# RF.net
KiCad netlist of a schematic drawn in Altium Designer
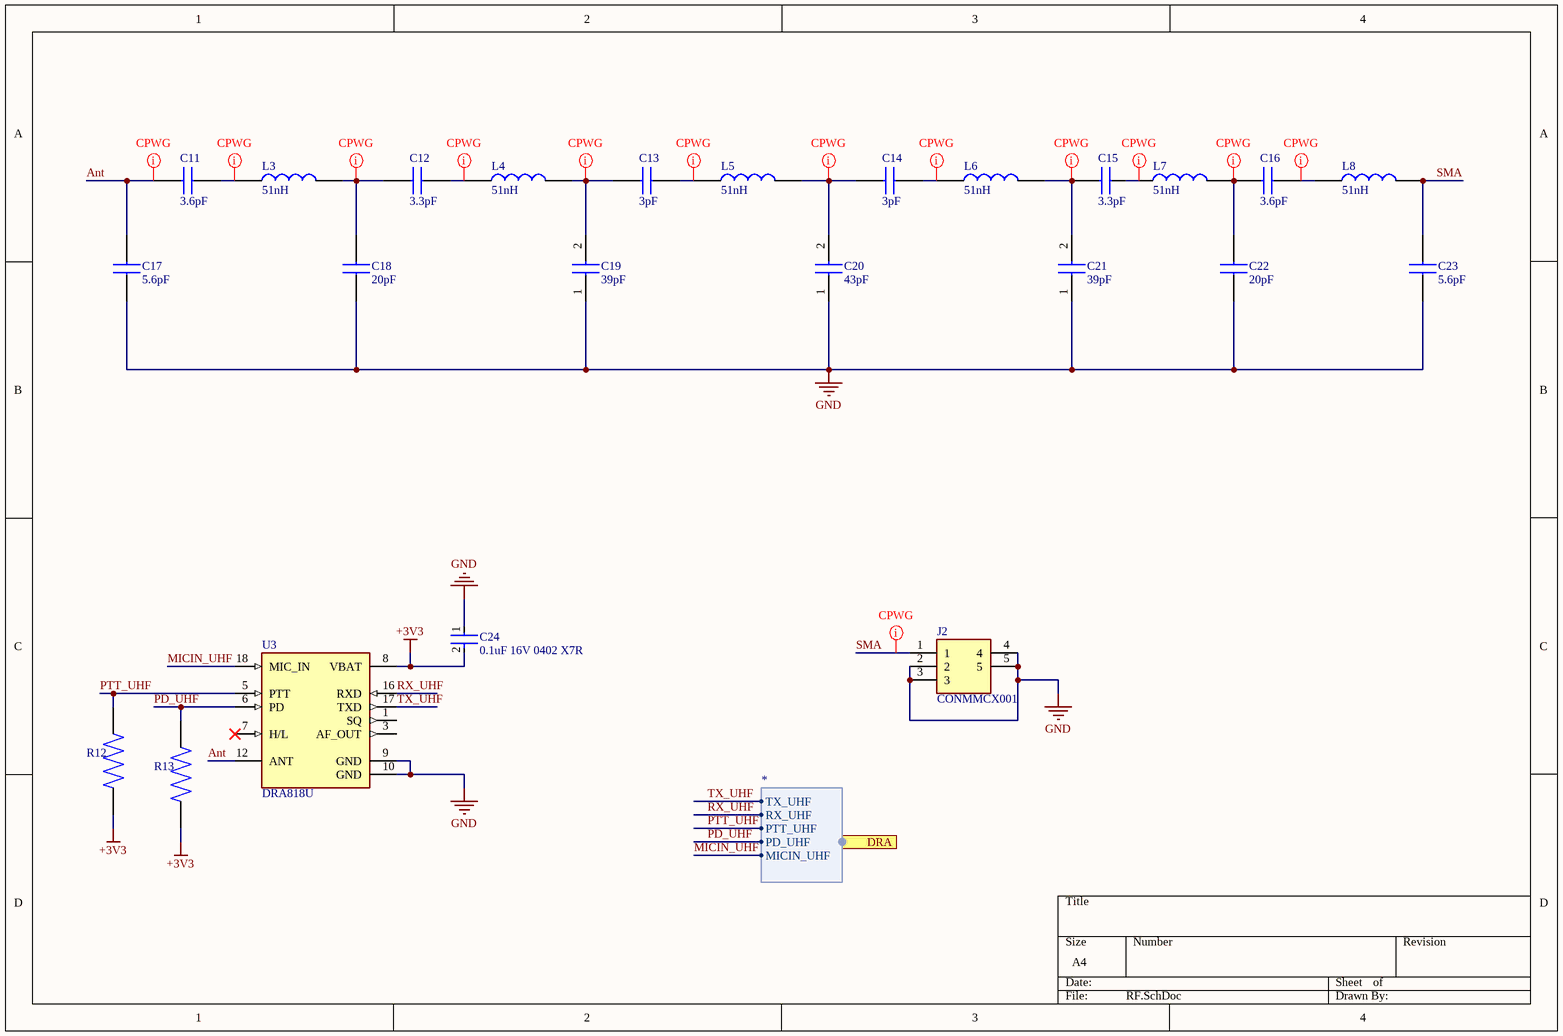
[diagram p0: RF.SchDoc]

(export (version "E")
  (design (tool "Eeschema 10.0.6"))
  (components
    (comp (ref "C11")
      (value "3.6pF")
      (footprint "CAP0603S")
      (fields (field (name "MANUFACTURER_PART_NUMBER") "CBR06C369BAGAC"))
      (libsource (lib "CBR06C369BAGAC") (part "CBR06C369BAGAC"))
    )
    (comp (ref "C12")
      (value "3.3pF")
      (footprint "CAP0603S")
      (description "Vishay 0603 VJ 3.3pF Ceramic Multilayer Capacitor, 250 V, +125C, COG Dielectric, +/-0.1pF SMD")
      (fields (field (name "MANUFACTURER_PART_NUMBER") "VJ0603D3R3BXPAJ"))
      (libsource (lib "VJ0603D3R3BXPAJ") (part "VJ0603D3R3BXPAJ"))
    )
    (comp (ref "C13")
      (value "3pF")
      (footprint "CAP0402S")
      (fields (field (name "MANUFACTURER_PART_NUMBER") "VJ0603D3R3BXPAJ"))
      (libsource (lib "VJ0603D3R3BXPAJ") (part "VJ0603D3R3BXPAJ"))
    )
    (comp (ref "C14")
      (value "3pF")
      (footprint "CAP0402S")
      (fields (field (name "MANUFACTURER_PART_NUMBER") "VJ0603D3R3BXPAJ"))
      (libsource (lib "VJ0603D3R3BXPAJ") (part "VJ0603D3R3BXPAJ"))
    )
    (comp (ref "C15")
      (value "3.3pF")
      (footprint "CAP0603S")
      (description "Vishay 0603 VJ 3.3pF Ceramic Multilayer Capacitor, 250 V, +125C, COG Dielectric, +/-0.1pF SMD")
      (fields (field (name "MANUFACTURER_PART_NUMBER") "VJ0603D3R3BXPAJ"))
      (libsource (lib "VJ0603D3R3BXPAJ") (part "VJ0603D3R3BXPAJ"))
    )
    (comp (ref "C16")
      (value "3.6pF")
      (footprint "CAP0603S")
      (fields (field (name "MANUFACTURER_PART_NUMBER") "CBR06C369BAGAC"))
      (libsource (lib "CBR06C369BAGAC") (part "CBR06C369BAGAC"))
    )
    (comp (ref "C17")
      (value "5.6pF")
      (footprint "CAP0603S")
      (description "AVX 0603 U 5.6pF Ceramic Multilayer Capacitor, 200 V dc, +125C, C0G Dielectric, +/-0.25pF SMD")
      (fields
        (field (name "MOUSER PART NUMBER") "581-06032U5R6CAT2A")
        (field (name "MANUFACTURER_PART_NUMBER") "06032U5R6CAT2A")
      )
      (libsource (lib "06032U5R6CAT2A") (part "06032U5R6CAT2A"))
    )
    (comp (ref "C18")
      (value "20pF")
      (footprint "CAP0603S")
      (fields (field (name "MANUFACTURER_PART_NUMBER") "CBR02C200F5GAC"))
      (libsource (lib "CBR02C200F5GAC") (part "CBR02C200F5GAC"))
    )
    (comp (ref "C19")
      (value "39pF")
      (footprint "CAP0603S")
      (description "Capacitor-C0603H390J5GACTU")
      (fields (field (name "MANUFACTURER_PART_NUMBER") "C0603H390J5GACTU"))
      (libsource (lib "*") (part "C0603H390J5GACTU"))
    )
    (comp (ref "C20")
      (value "43pF")
      (footprint "CAP0603S")
      (description "Capacitor")
      (fields
        (field (name "MANUFACTURER_PART_NUMBER") "CBR06C430J5GACAUTO")
        (field (name "MOUSER PART NUMBER") "80-CBR06C430J5GAUTO")
      )
      (libsource (lib "*") (part "CBR06C430J5GACAUTO"))
    )
    (comp (ref "C21")
      (value "39pF")
      (footprint "CAP0603S")
      (description "Capacitor")
      (fields (field (name "MANUFACTURER_PART_NUMBER") "C0603H390J5GACTU"))
      (libsource (lib "*") (part "C0603H390J5GACTU"))
    )
    (comp (ref "C22")
      (value "20pF")
      (footprint "CAP0603S")
      (fields (field (name "MANUFACTURER_PART_NUMBER") "CBR02C200F5GAC"))
      (libsource (lib "CBR02C200F5GAC") (part "CBR02C200F5GAC"))
    )
    (comp (ref "C23")
      (value "5.6pF")
      (footprint "CAP0603S")
      (description "AVX 0603 U 5.6pF Ceramic Multilayer Capacitor, 200 V dc, +125C, C0G Dielectric, +/-0.25pF SMD")
      (fields
        (field (name "MOUSER PART NUMBER") "581-06032U5R6CAT2A")
        (field (name "MANUFACTURER_PART_NUMBER") "06032U5R6CAT2A")
      )
      (libsource (lib "06032U5R6CAT2A") (part "06032U5R6CAT2A"))
    )
    (comp (ref "C24")
      (value "0.1uF 16V 0402 X7R")
      (footprint "CAP0402S")
      (description "CAP CER 0.1UF 16V X7R 0402")
      (fields (field (name "MANUFACTURER PART NUMBER") "GRM155R71C104KA88D") (field (name "TOLERANCE") "10%"))
      (libsource (lib "Miscellaneous Devices") (part "236180d848d6139a670b325ea6854c9"))
    )
    (comp (ref "J2")
      (value "CONMMCX001")
      (footprint "SAMTEC_MMCX-J-P-H-ST-SM1")
      (description "Body Features: Cable Connector Orientation Straight")
      (libsource (lib "CONMMCX001") (part "CONMMCX001"))
    )
    (comp (ref "L3")
      (value "51nH")
      (footprint "IND0603S")
      (description "Murata LQQ18A Series Wire-wound SMD Inductor with a Ferrite Core, 0.051 uH +/-2% 370mA Idc Q:38")
      (fields
        (field (name "MOUSER PART NUMBER") "81-LQW18AN51NG00D")
        (field (name "MANUFACTURER_PART_NUMBER") "LQW18AN51NG00D")
      )
      (libsource (lib "LQW18AN51NG00D") (part "LQW18AN51NG00D"))
    )
    (comp (ref "L4")
      (value "51nH")
      (footprint "IND0603S")
      (description "Murata LQQ18A Series Wire-wound SMD Inductor with a Ferrite Core, 0.051 uH +/-2% 370mA Idc Q:38")
      (fields
        (field (name "MOUSER PART NUMBER") "81-LQW18AN51NG00D")
        (field (name "MANUFACTURER_PART_NUMBER") "LQW18AN51NG00D")
      )
      (libsource (lib "LQW18AN51NG00D") (part "LQW18AN51NG00D"))
    )
    (comp (ref "L5")
      (value "51nH")
      (footprint "IND0603S")
      (description "Murata LQQ18A Series Wire-wound SMD Inductor with a Ferrite Core, 0.051 uH +/-2% 370mA Idc Q:38")
      (fields
        (field (name "MOUSER PART NUMBER") "81-LQW18AN51NG00D")
        (field (name "MANUFACTURER_PART_NUMBER") "LQW18AN51NG00D")
      )
      (libsource (lib "LQW18AN51NG00D") (part "LQW18AN51NG00D"))
    )
    (comp (ref "L6")
      (value "51nH")
      (footprint "IND0603S")
      (description "Murata LQQ18A Series Wire-wound SMD Inductor with a Ferrite Core, 0.051 uH +/-2% 370mA Idc Q:38")
      (fields
        (field (name "MOUSER PART NUMBER") "81-LQW18AN51NG00D")
        (field (name "MANUFACTURER_PART_NUMBER") "LQW18AN51NG00D")
      )
      (libsource (lib "LQW18AN51NG00D") (part "LQW18AN51NG00D"))
    )
    (comp (ref "L7")
      (value "51nH")
      (footprint "IND0603S")
      (description "Murata LQQ18A Series Wire-wound SMD Inductor with a Ferrite Core, 0.051 uH +/-2% 370mA Idc Q:38")
      (fields
        (field (name "MOUSER PART NUMBER") "81-LQW18AN51NG00D")
        (field (name "MANUFACTURER_PART_NUMBER") "LQW18AN51NG00D")
      )
      (libsource (lib "LQW18AN51NG00D") (part "LQW18AN51NG00D"))
    )
    (comp (ref "L8")
      (value "51nH")
      (footprint "IND0603S")
      (description "Murata LQQ18A Series Wire-wound SMD Inductor with a Ferrite Core, 0.051 uH +/-2% 370mA Idc Q:38")
      (fields
        (field (name "MOUSER PART NUMBER") "81-LQW18AN51NG00D")
        (field (name "MANUFACTURER_PART_NUMBER") "LQW18AN51NG00D")
      )
      (libsource (lib "LQW18AN51NG00D") (part "LQW18AN51NG00D"))
    )
    (comp (ref "R12")
      (value "CRCW060310K0FKEAC")
      (footprint "RES0603S")
      (description "10 kOhms Â±1% 0.1W, 1/10W Chip Resistor 0603 (1608 Metric) Thick Film")
      (fields (field (name "MF") "Vishay Dale"))
      (libsource (lib "CRCW060310K0FKEAC") (part "CRCW060310K0FKEAC"))
    )
    (comp (ref "R13")
      (value "CRCW060310K0FKEAC")
      (footprint "RES0603S")
      (description "10 kOhms Â±1% 0.1W, 1/10W Chip Resistor 0603 (1608 Metric) Thick Film")
      (fields (field (name "MF") "Vishay Dale"))
      (libsource (lib "CRCW060310K0FKEAC") (part "CRCW060310K0FKEAC"))
    )
    (comp (ref "U3")
      (value "DRA818U")
      (footprint "DRA818U")
      (description "UHF Band Voice Transceiver Module")
      (fields (field (name "MF") "DORJI") (field (name "MP") "DRA818V"))
      (libsource (lib "DRA818 Library") (part "DRA818V"))
    )
  )
  (nets
    (net (code "2") (name "+3V3") (class "Default")
      (node (ref "C24") (pin "2") (pinfunction "2_2") (pintype "passive"))
      (node (ref "R12") (pin "1") (pinfunction "1_1") (pintype "passive"))
      (node (ref "R13") (pin "1") (pinfunction "1_1") (pintype "passive"))
      (node (ref "U3") (pin "8") (pinfunction "VBAT_8") (pintype "power_in"))
    )
    (net (code "3") (name "/Ant") (class "Default")
      (node (ref "C11") (pin "1") (pinfunction "1_1") (pintype "passive"))
      (node (ref "C17") (pin "2") (pinfunction "2_2") (pintype "passive"))
      (node (ref "U3") (pin "12") (pinfunction "ANT_12") (pintype "passive"))
    )
    (net (code "4") (name "/MICIN_UHF") (class "Default")
      (node (ref "U3") (pin "18") (pinfunction "MIC_IN_18") (pintype "input"))
    )
    (net (code "5") (name "/PD_UHF") (class "Default")
      (node (ref "R13") (pin "2") (pinfunction "2_2") (pintype "passive"))
      (node (ref "U3") (pin "6") (pinfunction "PD_6") (pintype "input"))
    )
    (net (code "6") (name "/PTT_UHF") (class "Default")
      (node (ref "R12") (pin "2") (pinfunction "2_2") (pintype "passive"))
      (node (ref "U3") (pin "5") (pinfunction "PTT_5") (pintype "input"))
    )
    (net (code "7") (name "/RX_UHF") (class "Default")
      (node (ref "U3") (pin "16") (pinfunction "RXD_16") (pintype "input"))
    )
    (net (code "8") (name "/SMA") (class "Default")
      (node (ref "C23") (pin "2") (pinfunction "2_2") (pintype "passive"))
      (node (ref "J2") (pin "1") (pinfunction "1_1") (pintype "passive"))
      (node (ref "L8") (pin "2") (pinfunction "2_2") (pintype "passive"))
    )
    (net (code "9") (name "/TX_UHF") (class "Default")
      (node (ref "U3") (pin "17") (pinfunction "TXD_17") (pintype "output"))
    )
    (net (code "11") (name "GND") (class "Default")
      (node (ref "C17") (pin "1") (pinfunction "1_1") (pintype "passive"))
      (node (ref "C18") (pin "1") (pinfunction "1_1") (pintype "passive"))
      (node (ref "C19") (pin "1") (pinfunction "1_1") (pintype "passive"))
      (node (ref "C20") (pin "1") (pinfunction "1_1") (pintype "passive"))
      (node (ref "C21") (pin "1") (pinfunction "1_1") (pintype "passive"))
      (node (ref "C22") (pin "1") (pinfunction "1_1") (pintype "passive"))
      (node (ref "C23") (pin "1") (pinfunction "1_1") (pintype "passive"))
      (node (ref "C24") (pin "1") (pinfunction "1_1") (pintype "passive"))
      (node (ref "J2") (pin "2") (pinfunction "2_2") (pintype "passive"))
      (node (ref "J2") (pin "3") (pinfunction "3_3") (pintype "passive"))
      (node (ref "J2") (pin "4") (pinfunction "4_4") (pintype "passive"))
      (node (ref "J2") (pin "5") (pinfunction "5_5") (pintype "passive"))
      (node (ref "U3") (pin "10") (pinfunction "GND_10") (pintype "power_in"))
      (node (ref "U3") (pin "9") (pinfunction "GND_9") (pintype "power_in"))
    )
    (net (code "12") (name "Net-(C11-Pad2)") (class "Default")
      (node (ref "C11") (pin "2") (pinfunction "2_2") (pintype "passive"))
      (node (ref "L3") (pin "1") (pinfunction "1_1") (pintype "passive"))
    )
    (net (code "13") (name "Net-(C12-Pad1)") (class "Default")
      (node (ref "C12") (pin "1") (pinfunction "1_1") (pintype "passive"))
      (node (ref "C18") (pin "2") (pinfunction "2_2") (pintype "passive"))
      (node (ref "L3") (pin "2") (pinfunction "2_2") (pintype "passive"))
    )
    (net (code "14") (name "Net-(C12-Pad2)") (class "Default")
      (node (ref "C12") (pin "2") (pinfunction "2_2") (pintype "passive"))
      (node (ref "L4") (pin "1") (pinfunction "1_1") (pintype "passive"))
    )
    (net (code "15") (name "Net-(C13-Pad1)") (class "Default")
      (node (ref "C13") (pin "1") (pinfunction "1_1") (pintype "passive"))
      (node (ref "C19") (pin "2") (pinfunction "2_2") (pintype "passive"))
      (node (ref "L4") (pin "2") (pinfunction "2_2") (pintype "passive"))
    )
    (net (code "16") (name "Net-(C13-Pad2)") (class "Default")
      (node (ref "C13") (pin "2") (pinfunction "2_2") (pintype "passive"))
      (node (ref "L5") (pin "1") (pinfunction "1_1") (pintype "passive"))
    )
    (net (code "17") (name "Net-(C14-Pad1)") (class "Default")
      (node (ref "C14") (pin "1") (pinfunction "1_1") (pintype "passive"))
      (node (ref "C20") (pin "2") (pinfunction "2_2") (pintype "passive"))
      (node (ref "L5") (pin "2") (pinfunction "2_2") (pintype "passive"))
    )
    (net (code "18") (name "Net-(C14-Pad2)") (class "Default")
      (node (ref "C14") (pin "2") (pinfunction "2_2") (pintype "passive"))
      (node (ref "L6") (pin "1") (pinfunction "1_1") (pintype "passive"))
    )
    (net (code "19") (name "Net-(C15-Pad1)") (class "Default")
      (node (ref "C15") (pin "1") (pinfunction "1_1") (pintype "passive"))
      (node (ref "C21") (pin "2") (pinfunction "2_2") (pintype "passive"))
      (node (ref "L6") (pin "2") (pinfunction "2_2") (pintype "passive"))
    )
    (net (code "20") (name "Net-(C15-Pad2)") (class "Default")
      (node (ref "C15") (pin "2") (pinfunction "2_2") (pintype "passive"))
      (node (ref "L7") (pin "1") (pinfunction "1_1") (pintype "passive"))
    )
    (net (code "21") (name "Net-(C16-Pad1)") (class "Default")
      (node (ref "C16") (pin "1") (pinfunction "1_1") (pintype "passive"))
      (node (ref "C22") (pin "2") (pinfunction "2_2") (pintype "passive"))
      (node (ref "L7") (pin "2") (pinfunction "2_2") (pintype "passive"))
    )
    (net (code "22") (name "Net-(C16-Pad2)") (class "Default")
      (node (ref "C16") (pin "2") (pinfunction "2_2") (pintype "passive"))
      (node (ref "L8") (pin "1") (pinfunction "1_1") (pintype "passive"))
    )
    (net (code "23") (name "unconnected-(U3-AF_OUT-Pad3)") (class "Default")
      (node (ref "U3") (pin "3") (pinfunction "AF_OUT_3") (pintype "output"))
    )
    (net (code "24") (name "unconnected-(U3-H{slash}L-Pad7)") (class "Default")
      (node (ref "U3") (pin "7") (pinfunction "H/L_7") (pintype "input+no_connect"))
    )
    (net (code "25") (name "unconnected-(U3-SQ-Pad1)") (class "Default")
      (node (ref "U3") (pin "1") (pinfunction "SQ_1") (pintype "output"))
    )
  )
)
